# DRV_BJT.net
KiCad netlist of a schematic drawn in Altium Designer
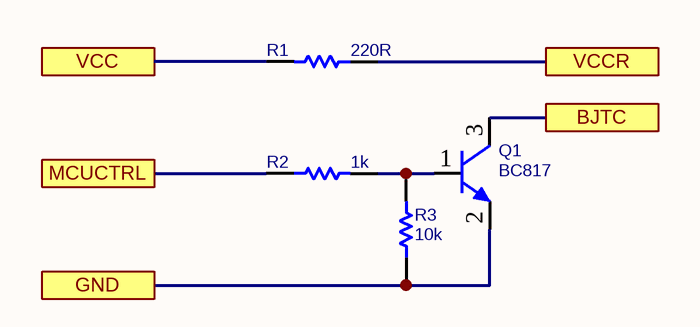
[diagram p0: DRV_BJT.SchDoc]

(export (version "E")
  (design (tool "Eeschema 10.0.6"))
  (components
    (comp (ref "Q1")
      (value "BC817")
      (footprint "SOT23_3")
      (description "BJT, NPN, 45v, 0.5A, SMD, SOT23")
      (fields (field (name "MANF") "NXP, ON"))
      (libsource (lib "transistor_bjt") (part "NPN_BC817_SOT23"))
    )
    (comp (ref "R1")
      (value "220R")
      (footprint "R0603")
      (description "RESISTOR, SMD, 1206")
      (libsource (lib "passive_smd") (part "RES_SMD_1206"))
    )
    (comp (ref "R2")
      (value "1k")
      (footprint "R0603")
      (description "RESISTOR, SMD")
      (libsource (lib "passive_smd") (part "RES_SMD_0603"))
    )
    (comp (ref "R3")
      (value "10k")
      (footprint "R0603")
      (description "RESISTOR, SMD")
      (libsource (lib "passive_smd") (part "RES_SMD_0603"))
    )
  )
  (nets
    (net (code "1") (name "/BJTC") (class "Default")
      (node (ref "Q1") (pin "3") (pinfunction "C_3") (pintype "passive"))
    )
    (net (code "2") (name "/GND") (class "Default")
      (node (ref "Q1") (pin "2") (pinfunction "E_2") (pintype "passive"))
      (node (ref "R3") (pin "1") (pinfunction "1_1") (pintype "passive"))
    )
    (net (code "3") (name "/MCUCTRL") (class "Default")
      (node (ref "R2") (pin "1") (pinfunction "1_1") (pintype "passive"))
    )
    (net (code "4") (name "/VCC") (class "Default")
      (node (ref "R1") (pin "2") (pinfunction "2_2") (pintype "passive"))
    )
    (net (code "5") (name "/VCCR") (class "Default")
      (node (ref "R1") (pin "1") (pinfunction "1_1") (pintype "passive"))
    )
    (net (code "6") (name "Net-(Q1-B)") (class "Default")
      (node (ref "Q1") (pin "1") (pinfunction "B_1") (pintype "passive"))
      (node (ref "R2") (pin "2") (pinfunction "2_2") (pintype "passive"))
      (node (ref "R3") (pin "2") (pinfunction "2_2") (pintype "passive"))
    )
  )
)
